# Sch_Mang_giao_thuc_Iot.net
KiCad netlist of a schematic drawn in Altium Designer
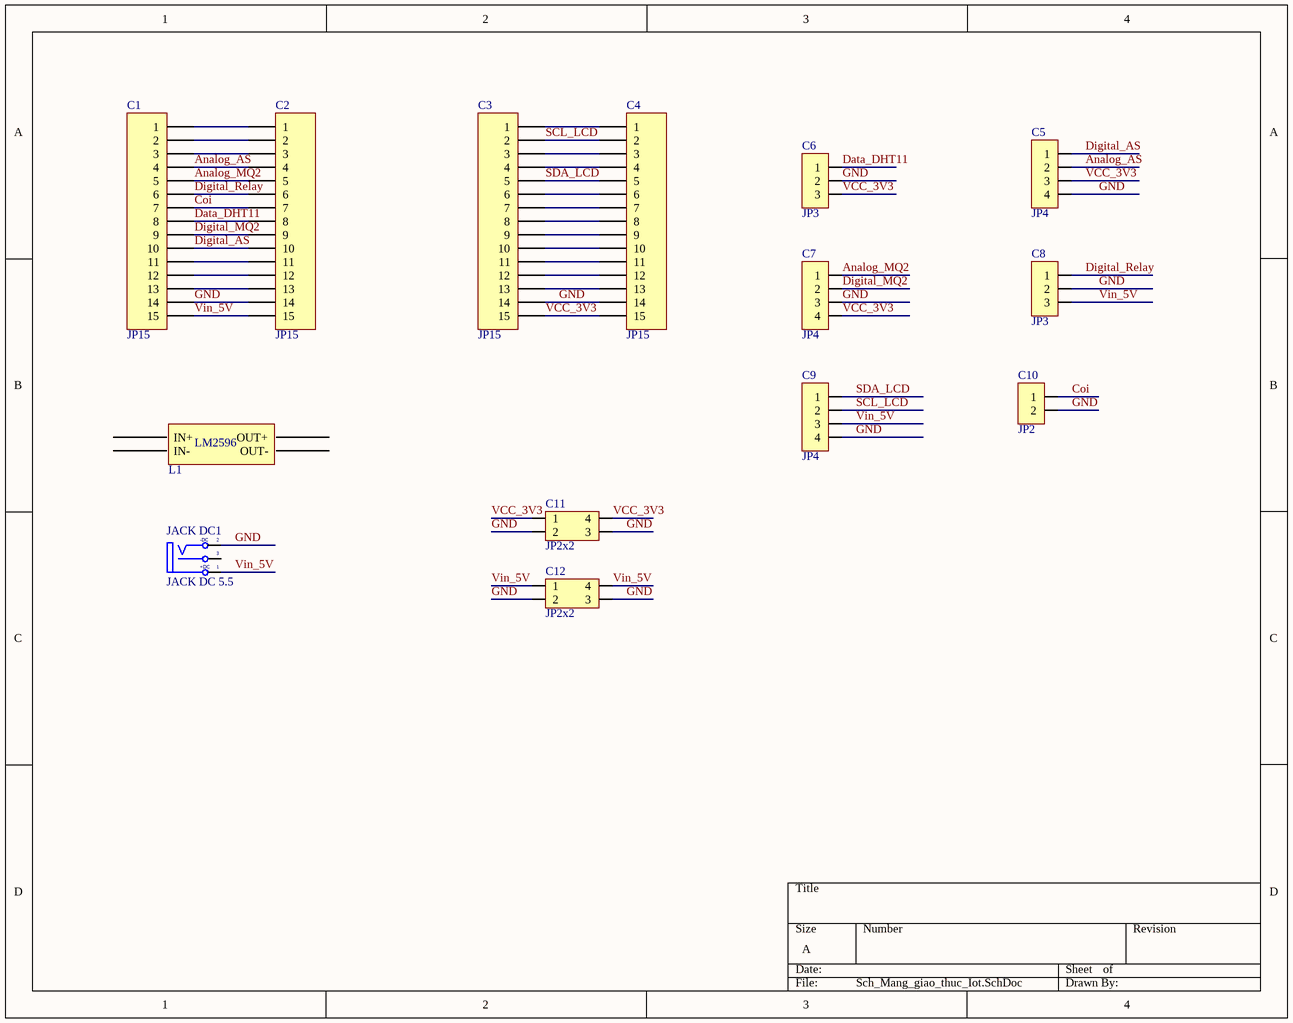
[diagram p0: Sch_Mang_giao_thuc_Iot.SchDoc]

(export (version "E")
  (design (tool "Eeschema 10.0.6"))
  (components
    (comp (ref "C1")
      (value "JP15")
      (footprint "JP15-C1T")
      (description "WR-PHD 2.54 mm Angled Socket Header")
      (fields
        (field (name "MANUFACTURER") "Würth Elektronik eiSos GmbH")
        (field (name "PARTNO") "613015143121")
        (field (name "CREATED BY") "Karrer Zheng")
      )
      (libsource (lib "") (part "JP15_1"))
    )
    (comp (ref "C2")
      (value "JP15")
      (footprint "JP15-C1T")
      (description "WR-PHD 2.54 mm Angled Socket Header")
      (fields
        (field (name "MANUFACTURER") "Würth Elektronik eiSos GmbH")
        (field (name "PARTNO") "613015143121")
        (field (name "CREATED BY") "Karrer Zheng")
      )
      (libsource (lib "KhanhBK_Library_3") (part "JP15"))
    )
    (comp (ref "C3")
      (value "JP15")
      (footprint "JP15-C1T")
      (description "WR-PHD 2.54 mm Angled Socket Header")
      (fields
        (field (name "MANUFACTURER") "Würth Elektronik eiSos GmbH")
        (field (name "PARTNO") "613015143121")
        (field (name "CREATED BY") "Karrer Zheng")
      )
      (libsource (lib "") (part "JP15_1"))
    )
    (comp (ref "C4")
      (value "JP15")
      (footprint "JP15-C1T")
      (description "WR-PHD 2.54 mm Angled Socket Header")
      (fields
        (field (name "MANUFACTURER") "Würth Elektronik eiSos GmbH")
        (field (name "PARTNO") "613015143121")
        (field (name "CREATED BY") "Karrer Zheng")
      )
      (libsource (lib "KhanhBK_Library_3") (part "JP15"))
    )
    (comp (ref "C5")
      (value "JP4")
      (footprint "JP4-C1T")
      (description "WR-PHD 2.54 mm Angled Socket Header")
      (fields
        (field (name "MANUFACTURER") "Würth Elektronik eiSos GmbH")
        (field (name "PARTNO") "613004143121")
        (field (name "CREATED BY") "Karrer Zheng")
      )
      (libsource (lib "KhanhBK_Library_3") (part "JP4"))
    )
    (comp (ref "C6")
      (value "JP3")
      (footprint "JP3-C1T")
      (description "WR-PHD 2.54 mm Angled Socket Header")
      (fields
        (field (name "MANUFACTURER") "Würth Elektronik eiSos GmbH")
        (field (name "PARTNO") "613003143121")
        (field (name "CREATED BY") "Karrer Zheng")
      )
      (libsource (lib "KhanhBK_Library_3") (part "JP3"))
    )
    (comp (ref "C7")
      (value "JP4")
      (footprint "JP4-C1T")
      (description "WR-PHD 2.54 mm Angled Socket Header")
      (fields
        (field (name "MANUFACTURER") "Würth Elektronik eiSos GmbH")
        (field (name "PARTNO") "613004143121")
        (field (name "CREATED BY") "Karrer Zheng")
      )
      (libsource (lib "KhanhBK_Library_3") (part "JP4"))
    )
    (comp (ref "C8")
      (value "JP3")
      (footprint "JP3-C1T")
      (description "WR-PHD 2.54 mm Angled Socket Header")
      (fields
        (field (name "MANUFACTURER") "Würth Elektronik eiSos GmbH")
        (field (name "PARTNO") "613003143121")
        (field (name "CREATED BY") "Karrer Zheng")
      )
      (libsource (lib "KhanhBK_Library_3") (part "JP3"))
    )
    (comp (ref "C9")
      (value "JP4")
      (footprint "JP4-C1T")
      (description "WR-PHD 2.54 mm Angled Socket Header")
      (fields
        (field (name "MANUFACTURER") "Würth Elektronik eiSos GmbH")
        (field (name "PARTNO") "613004143121")
        (field (name "CREATED BY") "Karrer Zheng")
      )
      (libsource (lib "KhanhBK_Library_3") (part "JP4"))
    )
    (comp (ref "C10")
      (value "JP2")
      (footprint "JP2-C1T")
      (description "WR-PHD 2.54 mm Angled Socket Header")
      (fields
        (field (name "MANUFACTURER") "Würth Elektronik eiSos GmbH")
        (field (name "PARTNO") "613002143121")
        (field (name "CREATED BY") "Karrer Zheng")
      )
      (libsource (lib "KhanhBK_Library_3") (part "JP2"))
    )
    (comp (ref "C11")
      (value "JP2x2")
      (footprint "JP2-C2T")
      (description "WR-PHD 2.54 mm Dual Socket Header")
      (fields
        (field (name "MANUFACTURER") "Würth Elektronik eiSos GmbH")
        (field (name "PARTNO") "61300421821")
        (field (name "CREATED BY") "Karrer Zheng")
      )
      (libsource (lib "KhanhBK_Library_3") (part "JP2x2"))
    )
    (comp (ref "C12")
      (value "JP2x2")
      (footprint "JP2-C2T")
      (description "WR-PHD 2.54 mm Dual Socket Header")
      (fields
        (field (name "MANUFACTURER") "Würth Elektronik eiSos GmbH")
        (field (name "PARTNO") "61300421821")
        (field (name "CREATED BY") "Karrer Zheng")
      )
      (libsource (lib "KhanhBK_Library_3") (part "JP2x2"))
    )
    (comp (ref "JACK DC1")
      (value "JACK DC 5.5")
      (footprint "JACK DC 5.5")
      (libsource (lib "Altium_Lib_by_KhueNguyenCreator") (part "JACK DC 5.5"))
    )
    (comp (ref "L1")
      (value "BUCK_LM2596")
      (footprint "BUCK_LM2596")
      (libsource (lib "BUCK_LM2596_Library") (part "BUCK_LM2596"))
    )
  )
  (nets
    (net (code "1") (name "/Analog_AS") (class "Default")
      (node (ref "C1") (pin "4") (pinfunction "4_4") (pintype "passive"))
      (node (ref "C2") (pin "4") (pinfunction "4_4") (pintype "passive"))
      (node (ref "C5") (pin "2") (pinfunction "2_2") (pintype "passive"))
    )
    (net (code "2") (name "/Analog_MQ2") (class "Default")
      (node (ref "C1") (pin "5") (pinfunction "5_5") (pintype "passive"))
      (node (ref "C2") (pin "5") (pinfunction "5_5") (pintype "passive"))
      (node (ref "C7") (pin "1") (pinfunction "1_1") (pintype "passive"))
    )
    (net (code "3") (name "/Coi") (class "Default")
      (node (ref "C1") (pin "7") (pinfunction "7_7") (pintype "passive"))
      (node (ref "C10") (pin "1") (pinfunction "1_1") (pintype "passive"))
      (node (ref "C2") (pin "7") (pinfunction "7_7") (pintype "passive"))
    )
    (net (code "4") (name "/Data_DHT11") (class "Default")
      (node (ref "C1") (pin "8") (pinfunction "8_8") (pintype "passive"))
      (node (ref "C2") (pin "8") (pinfunction "8_8") (pintype "passive"))
      (node (ref "C6") (pin "1") (pinfunction "1_1") (pintype "passive"))
    )
    (net (code "5") (name "/Digital_AS") (class "Default")
      (node (ref "C1") (pin "10") (pinfunction "10_10") (pintype "passive"))
      (node (ref "C2") (pin "10") (pinfunction "10_10") (pintype "passive"))
      (node (ref "C5") (pin "1") (pinfunction "1_1") (pintype "passive"))
    )
    (net (code "6") (name "/Digital_MQ2") (class "Default")
      (node (ref "C1") (pin "9") (pinfunction "9_9") (pintype "passive"))
      (node (ref "C2") (pin "9") (pinfunction "9_9") (pintype "passive"))
      (node (ref "C7") (pin "2") (pinfunction "2_2") (pintype "passive"))
    )
    (net (code "7") (name "/Digital_Relay") (class "Default")
      (node (ref "C1") (pin "6") (pinfunction "6_6") (pintype "passive"))
      (node (ref "C2") (pin "6") (pinfunction "6_6") (pintype "passive"))
      (node (ref "C8") (pin "1") (pinfunction "1_1") (pintype "passive"))
    )
    (net (code "8") (name "/GND") (class "Default")
      (node (ref "C1") (pin "14") (pinfunction "14_14") (pintype "passive"))
      (node (ref "C10") (pin "2") (pinfunction "2_2") (pintype "passive"))
      (node (ref "C11") (pin "2") (pinfunction "2_2") (pintype "passive"))
      (node (ref "C11") (pin "3") (pinfunction "3_3") (pintype "passive"))
      (node (ref "C12") (pin "2") (pinfunction "2_2") (pintype "passive"))
      (node (ref "C12") (pin "3") (pinfunction "3_3") (pintype "passive"))
      (node (ref "C2") (pin "14") (pinfunction "14_14") (pintype "passive"))
      (node (ref "C3") (pin "14") (pinfunction "14_14") (pintype "passive"))
      (node (ref "C4") (pin "14") (pinfunction "14_14") (pintype "passive"))
      (node (ref "C5") (pin "4") (pinfunction "4_4") (pintype "passive"))
      (node (ref "C6") (pin "2") (pinfunction "2_2") (pintype "passive"))
      (node (ref "C7") (pin "3") (pinfunction "3_3") (pintype "passive"))
      (node (ref "C8") (pin "2") (pinfunction "2_2") (pintype "passive"))
      (node (ref "C9") (pin "4") (pinfunction "4_4") (pintype "passive"))
      (node (ref "JACK DC1") (pin "2") (pinfunction "TN_2") (pintype "passive"))
    )
    (net (code "9") (name "/SCL_LCD") (class "Default")
      (node (ref "C3") (pin "2") (pinfunction "2_2") (pintype "passive"))
      (node (ref "C4") (pin "2") (pinfunction "2_2") (pintype "passive"))
      (node (ref "C9") (pin "2") (pinfunction "2_2") (pintype "passive"))
    )
    (net (code "10") (name "/SDA_LCD") (class "Default")
      (node (ref "C3") (pin "5") (pinfunction "5_5") (pintype "passive"))
      (node (ref "C4") (pin "5") (pinfunction "5_5") (pintype "passive"))
      (node (ref "C9") (pin "1") (pinfunction "1_1") (pintype "passive"))
    )
    (net (code "11") (name "/VCC_3V3") (class "Default")
      (node (ref "C11") (pin "1") (pinfunction "1_1") (pintype "passive"))
      (node (ref "C11") (pin "4") (pinfunction "4_4") (pintype "passive"))
      (node (ref "C3") (pin "15") (pinfunction "15_15") (pintype "passive"))
      (node (ref "C4") (pin "15") (pinfunction "15_15") (pintype "passive"))
      (node (ref "C5") (pin "3") (pinfunction "3_3") (pintype "passive"))
      (node (ref "C6") (pin "3") (pinfunction "3_3") (pintype "passive"))
      (node (ref "C7") (pin "4") (pinfunction "4_4") (pintype "passive"))
    )
    (net (code "12") (name "/Vin_5V") (class "Default")
      (node (ref "C1") (pin "15") (pinfunction "15_15") (pintype "passive"))
      (node (ref "C12") (pin "1") (pinfunction "1_1") (pintype "passive"))
      (node (ref "C12") (pin "4") (pinfunction "4_4") (pintype "passive"))
      (node (ref "C2") (pin "15") (pinfunction "15_15") (pintype "passive"))
      (node (ref "C8") (pin "3") (pinfunction "3_3") (pintype "passive"))
      (node (ref "C9") (pin "3") (pinfunction "3_3") (pintype "passive"))
      (node (ref "JACK DC1") (pin "1") (pinfunction "T_1") (pintype "passive"))
    )
    (net (code "13") (name "Net-(C1-Pad1)") (class "Default")
      (node (ref "C1") (pin "1") (pinfunction "1_1") (pintype "passive"))
      (node (ref "C2") (pin "1") (pinfunction "1_1") (pintype "passive"))
    )
    (net (code "14") (name "Net-(C1-Pad2)") (class "Default")
      (node (ref "C1") (pin "2") (pinfunction "2_2") (pintype "passive"))
      (node (ref "C2") (pin "2") (pinfunction "2_2") (pintype "passive"))
    )
    (net (code "15") (name "Net-(C1-Pad3)") (class "Default")
      (node (ref "C1") (pin "3") (pinfunction "3_3") (pintype "passive"))
      (node (ref "C2") (pin "3") (pinfunction "3_3") (pintype "passive"))
    )
    (net (code "16") (name "Net-(C1-Pad11)") (class "Default")
      (node (ref "C1") (pin "11") (pinfunction "11_11") (pintype "passive"))
      (node (ref "C2") (pin "11") (pinfunction "11_11") (pintype "passive"))
    )
    (net (code "17") (name "Net-(C1-Pad12)") (class "Default")
      (node (ref "C1") (pin "12") (pinfunction "12_12") (pintype "passive"))
      (node (ref "C2") (pin "12") (pinfunction "12_12") (pintype "passive"))
    )
    (net (code "18") (name "Net-(C1-Pad13)") (class "Default")
      (node (ref "C1") (pin "13") (pinfunction "13_13") (pintype "passive"))
      (node (ref "C2") (pin "13") (pinfunction "13_13") (pintype "passive"))
    )
    (net (code "19") (name "Net-(C3-Pad1)") (class "Default")
      (node (ref "C3") (pin "1") (pinfunction "1_1") (pintype "passive"))
      (node (ref "C4") (pin "1") (pinfunction "1_1") (pintype "passive"))
    )
    (net (code "20") (name "Net-(C3-Pad3)") (class "Default")
      (node (ref "C3") (pin "3") (pinfunction "3_3") (pintype "passive"))
      (node (ref "C4") (pin "3") (pinfunction "3_3") (pintype "passive"))
    )
    (net (code "21") (name "Net-(C3-Pad4)") (class "Default")
      (node (ref "C3") (pin "4") (pinfunction "4_4") (pintype "passive"))
      (node (ref "C4") (pin "4") (pinfunction "4_4") (pintype "passive"))
    )
    (net (code "22") (name "Net-(C3-Pad6)") (class "Default")
      (node (ref "C3") (pin "6") (pinfunction "6_6") (pintype "passive"))
      (node (ref "C4") (pin "6") (pinfunction "6_6") (pintype "passive"))
    )
    (net (code "23") (name "Net-(C3-Pad7)") (class "Default")
      (node (ref "C3") (pin "7") (pinfunction "7_7") (pintype "passive"))
      (node (ref "C4") (pin "7") (pinfunction "7_7") (pintype "passive"))
    )
    (net (code "24") (name "Net-(C3-Pad8)") (class "Default")
      (node (ref "C3") (pin "8") (pinfunction "8_8") (pintype "passive"))
      (node (ref "C4") (pin "8") (pinfunction "8_8") (pintype "passive"))
    )
    (net (code "25") (name "Net-(C3-Pad9)") (class "Default")
      (node (ref "C3") (pin "9") (pinfunction "9_9") (pintype "passive"))
      (node (ref "C4") (pin "9") (pinfunction "9_9") (pintype "passive"))
    )
    (net (code "26") (name "Net-(C3-Pad10)") (class "Default")
      (node (ref "C3") (pin "10") (pinfunction "10_10") (pintype "passive"))
      (node (ref "C4") (pin "10") (pinfunction "10_10") (pintype "passive"))
    )
    (net (code "27") (name "Net-(C3-Pad11)") (class "Default")
      (node (ref "C3") (pin "11") (pinfunction "11_11") (pintype "passive"))
      (node (ref "C4") (pin "11") (pinfunction "11_11") (pintype "passive"))
    )
    (net (code "28") (name "Net-(C3-Pad12)") (class "Default")
      (node (ref "C3") (pin "12") (pinfunction "12_12") (pintype "passive"))
      (node (ref "C4") (pin "12") (pinfunction "12_12") (pintype "passive"))
    )
    (net (code "29") (name "Net-(C3-Pad13)") (class "Default")
      (node (ref "C3") (pin "13") (pinfunction "13_13") (pintype "passive"))
      (node (ref "C4") (pin "13") (pinfunction "13_13") (pintype "passive"))
    )
    (net (code "30") (name "unconnected-(JACK DC1-S-Pad3)") (class "Default")
      (node (ref "JACK DC1") (pin "3") (pinfunction "S_3") (pintype "power_in"))
    )
    (net (code "31") (name "unconnected-(L1-IN+-Pad1)") (class "Default")
      (node (ref "L1") (pin "1") (pinfunction "IN+_1") (pintype "passive"))
    )
    (net (code "32") (name "unconnected-(L1-IN--Pad2)") (class "Default")
      (node (ref "L1") (pin "2") (pinfunction "IN-_2") (pintype "passive"))
    )
    (net (code "33") (name "unconnected-(L1-OUT+-Pad4)") (class "Default")
      (node (ref "L1") (pin "4") (pinfunction "OUT+_4") (pintype "passive"))
    )
    (net (code "34") (name "unconnected-(L1-OUT--Pad3)") (class "Default")
      (node (ref "L1") (pin "3") (pinfunction "OUT-_3") (pintype "passive"))
    )
  )
)
